# SparkFun_tDof-TMF8820_Mini.net
KiCad netlist of a schematic drawn in EAGLE
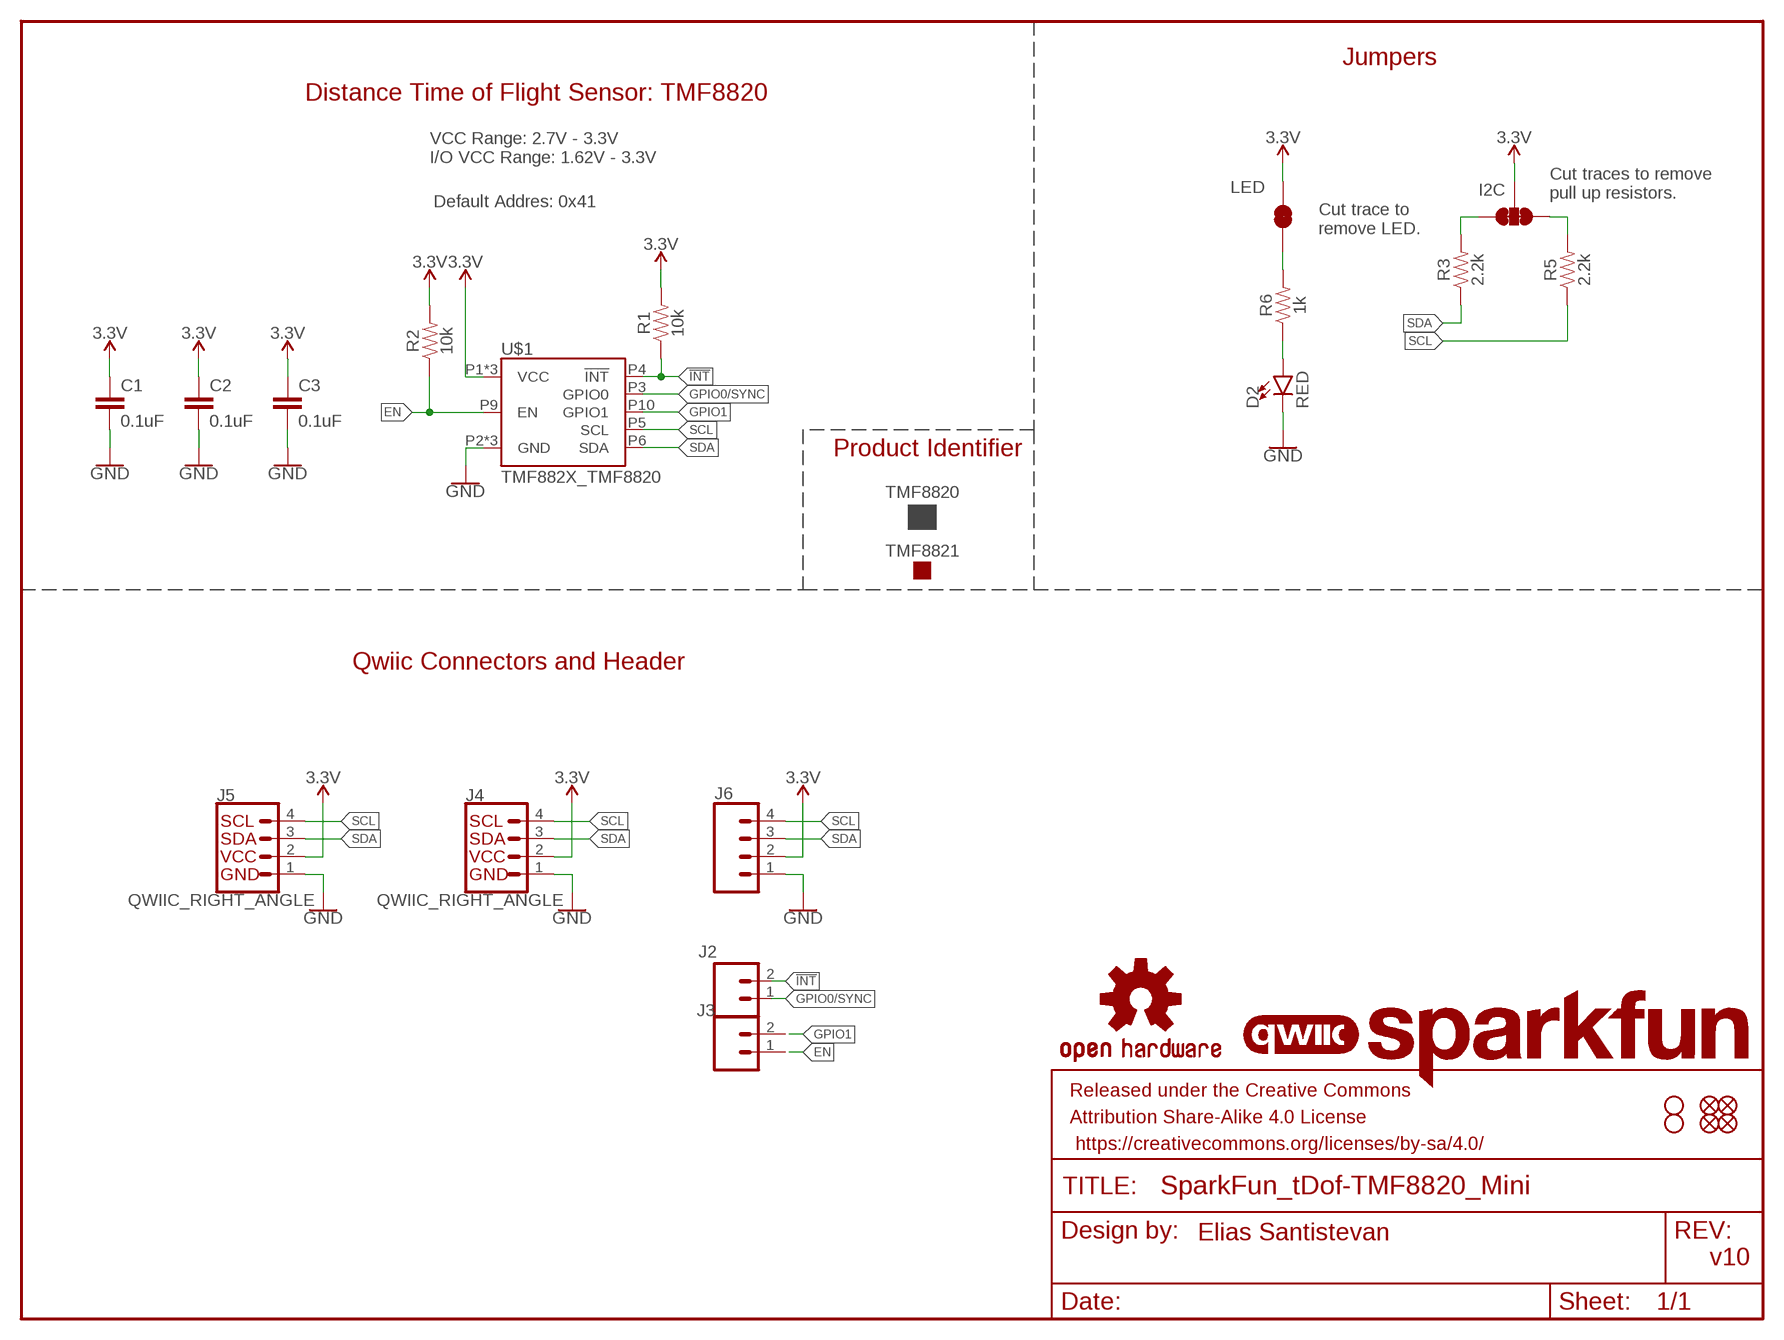
[diagram p0: schematic, sheet 1]

(export (version "E")
  (design (tool "Eeschema 10.0.6"))
  (components
    (comp (ref "C1")
      (value "0.1uF")
      (footprint "eagle-import:0402-TIGHT")
      (libsource (lib "eagle-import") (part "0.1UF-0402T-6.3V-10%-X7R"))
    )
    (comp (ref "C2")
      (value "0.1uF")
      (footprint "eagle-import:0402-TIGHT")
      (libsource (lib "eagle-import") (part "0.1UF-0402T-6.3V-10%-X7R"))
    )
    (comp (ref "C3")
      (value "0.1uF")
      (footprint "eagle-import:0402-TIGHT")
      (libsource (lib "eagle-import") (part "0.1UF-0402T-6.3V-10%-X7R"))
    )
    (comp (ref "D2")
      (value "RED")
      (footprint "eagle-import:LED-0603")
      (libsource (lib "eagle-import") (part "LED-RED0603"))
    )
    (comp (ref "FD5")
      (value "FIDUCIALUFIDUCIAL")
      (footprint "eagle-import:FIDUCIAL-MICRO")
      (libsource (lib "eagle-import") (part "FIDUCIALUFIDUCIAL"))
    )
    (comp (ref "FD6")
      (value "FIDUCIALUFIDUCIAL")
      (footprint "eagle-import:FIDUCIAL-MICRO")
      (libsource (lib "eagle-import") (part "FIDUCIALUFIDUCIAL"))
    )
    (comp (ref "FD7")
      (value "FIDUCIALUFIDUCIAL")
      (footprint "eagle-import:FIDUCIAL-MICRO")
      (libsource (lib "eagle-import") (part "FIDUCIALUFIDUCIAL"))
    )
    (comp (ref "FD8")
      (value "FIDUCIALUFIDUCIAL")
      (footprint "eagle-import:FIDUCIAL-MICRO")
      (libsource (lib "eagle-import") (part "FIDUCIALUFIDUCIAL"))
    )
    (comp (ref "FRAME2")
      (value "FRAME-LETTER")
      (footprint "eagle-import:CREATIVE_COMMONS")
      (libsource (lib "eagle-import") (part "FRAME-LETTER"))
    )
    (comp (ref "H7")
      (value "STAND-OFFTIGHT")
      (footprint "eagle-import:STAND-OFF-TIGHT")
      (libsource (lib "eagle-import") (part "STAND-OFFTIGHT"))
    )
    (comp (ref "H8")
      (value "STAND-OFFTIGHT")
      (footprint "eagle-import:STAND-OFF-TIGHT")
      (libsource (lib "eagle-import") (part "STAND-OFFTIGHT"))
    )
    (comp (ref "I2C")
      (value "I2C_PU")
      (footprint "eagle-import:SMT-JUMPER_3_2-NC_TRACE_SILK")
      (libsource (lib "eagle-import") (part "JUMPER-SMT_3_2-NC_TRACE_SILK"))
    )
    (comp (ref "J2")
      (value "CONN_021X02_NO_SILK")
      (footprint "eagle-import:1X02_NO_SILK")
      (libsource (lib "eagle-import") (part "CONN_021X02_NO_SILK"))
    )
    (comp (ref "J3")
      (value "CONN_021X02_NO_SILK")
      (footprint "eagle-import:1X02_NO_SILK")
      (libsource (lib "eagle-import") (part "CONN_021X02_NO_SILK"))
    )
    (comp (ref "J4")
      (value "QWIIC_RIGHT_ANGLE")
      (footprint "eagle-import:JST04_1MM_RA")
      (libsource (lib "eagle-import") (part "QWIIC_CONNECTORJS-1MM"))
    )
    (comp (ref "J5")
      (value "QWIIC_RIGHT_ANGLE")
      (footprint "eagle-import:JST04_1MM_RA")
      (libsource (lib "eagle-import") (part "QWIIC_CONNECTORJS-1MM"))
    )
    (comp (ref "J6")
      (value "CONN_041X04_NO_SILK")
      (footprint "eagle-import:1X04_NO_SILK")
      (libsource (lib "eagle-import") (part "CONN_041X04_NO_SILK"))
    )
    (comp (ref "LED")
      (value "LED")
      (footprint "eagle-import:SMT-JUMPER_2_NC_TRACE_SILK")
      (libsource (lib "eagle-import") (part "JUMPER-SMT_2_NC_TRACE_SILK"))
    )
    (comp (ref "LOGO1")
      (value "SFE_LOGO_NAMEBLANK")
      (footprint "eagle-import:BLANK")
      (libsource (lib "eagle-import") (part "SFE_LOGO_NAMEBLANK"))
    )
    (comp (ref "LOGO2")
      (value "QWIIC_LOGO_4MM")
      (footprint "eagle-import:QWIIC_4MM")
      (libsource (lib "eagle-import") (part "QWIIC_LOGO_4MM"))
    )
    (comp (ref "LOGO3")
      (value "OSHW-LOGONO_SILK")
      (footprint "eagle-import:DUMMY")
      (libsource (lib "eagle-import") (part "OSHW-LOGONO_SILK"))
    )
    (comp (ref "R1")
      (value "10k")
      (footprint "eagle-import:0402-TIGHT")
      (libsource (lib "eagle-import") (part "10KOHM-0402T-1/16W-1%"))
    )
    (comp (ref "R2")
      (value "10k")
      (footprint "eagle-import:0402-TIGHT")
      (libsource (lib "eagle-import") (part "10KOHM-0402T-1/16W-1%"))
    )
    (comp (ref "R3")
      (value "2.2k")
      (footprint "eagle-import:0402-TIGHT")
      (libsource (lib "eagle-import") (part "2.2KOHM-0402T-1/16W-1%"))
    )
    (comp (ref "R5")
      (value "2.2k")
      (footprint "eagle-import:0402-TIGHT")
      (libsource (lib "eagle-import") (part "2.2KOHM-0402T-1/16W-1%"))
    )
    (comp (ref "R6")
      (value "1k")
      (footprint "eagle-import:0402-TIGHT")
      (libsource (lib "eagle-import") (part "1KOHM-0402T-1/16W-1%"))
    )
    (comp (ref "TMF8820")
      (value "PROD_ID_PASTE_SILK")
      (footprint "eagle-import:PRODUCT_IDENT_PASTE_SILK")
      (libsource (lib "eagle-import") (part "PROD_ID_PASTE_SILK"))
    )
    (comp (ref "TMF8821")
      (value "PROD_ID_NO-PASTE_SILK")
      (footprint "eagle-import:PRODUCT_IDENT_NO_SILK")
      (libsource (lib "eagle-import") (part "PROD_ID_NO-PASTE_SILK"))
    )
    (comp (ref "U$1")
      (value "TMF882X_TMF8820")
      (footprint "eagle-import:TMF882X")
      (libsource (lib "eagle-import") (part "TMF882X_TMF8820"))
    )
  )
  (nets
    (net (code "1") (name "/~{INT}") (class "Default")
      (node (ref "J2") (pin "2") (pinfunction "2_2") (pintype "passive"))
      (node (ref "R1") (pin "1") (pinfunction "1_1") (pintype "passive"))
      (node (ref "U$1") (pin "P4") (pinfunction "~{INT}_P4") (pintype "bidirectional"))
    )
    (net (code "2") (name "3.3V") (class "Default")
      (node (ref "C1") (pin "1") (pinfunction "1_1") (pintype "passive"))
      (node (ref "C2") (pin "1") (pinfunction "1_1") (pintype "passive"))
      (node (ref "C3") (pin "1") (pinfunction "1_1") (pintype "passive"))
      (node (ref "I2C") (pin "2") (pinfunction "2_2") (pintype "passive"))
      (node (ref "J4") (pin "2") (pinfunction "2_2") (pintype "power_in"))
      (node (ref "J5") (pin "2") (pinfunction "2_2") (pintype "power_in"))
      (node (ref "J6") (pin "2") (pinfunction "2_2") (pintype "passive"))
      (node (ref "LED") (pin "2") (pinfunction "2_2") (pintype "passive"))
      (node (ref "R1") (pin "2") (pinfunction "2_2") (pintype "passive"))
      (node (ref "R2") (pin "2") (pinfunction "2_2") (pintype "passive"))
      (node (ref "U$1") (pin "P1") (pinfunction "VCC_P1") (pintype "power_in"))
      (node (ref "U$1") (pin "P12") (pinfunction "VCC_P12") (pintype "power_in"))
      (node (ref "U$1") (pin "P7") (pinfunction "VCC_P7") (pintype "power_in"))
    )
    (net (code "3") (name "EN") (class "Default")
      (node (ref "J3") (pin "1") (pinfunction "1_1") (pintype "passive"))
      (node (ref "R2") (pin "1") (pinfunction "1_1") (pintype "passive"))
      (node (ref "U$1") (pin "P9") (pinfunction "EN_P9") (pintype "input"))
    )
    (net (code "4") (name "GND") (class "Default")
      (node (ref "C1") (pin "2") (pinfunction "2_2") (pintype "passive"))
      (node (ref "C2") (pin "2") (pinfunction "2_2") (pintype "passive"))
      (node (ref "C3") (pin "2") (pinfunction "2_2") (pintype "passive"))
      (node (ref "D2") (pin "C") (pinfunction "C_C") (pintype "passive"))
      (node (ref "J4") (pin "1") (pinfunction "1_1") (pintype "power_in"))
      (node (ref "J5") (pin "1") (pinfunction "1_1") (pintype "power_in"))
      (node (ref "J6") (pin "1") (pinfunction "1_1") (pintype "passive"))
      (node (ref "U$1") (pin "P11") (pinfunction "GND_P11") (pintype "power_in"))
      (node (ref "U$1") (pin "P2") (pinfunction "GND_P2") (pintype "power_in"))
      (node (ref "U$1") (pin "P8") (pinfunction "GND_P8") (pintype "power_in"))
    )
    (net (code "5") (name "GPIO0{slash}SYNC") (class "Default")
      (node (ref "J2") (pin "1") (pinfunction "1_1") (pintype "passive"))
      (node (ref "U$1") (pin "P3") (pinfunction "GPIO0_P3") (pintype "bidirectional"))
    )
    (net (code "6") (name "GPIO1") (class "Default")
      (node (ref "J3") (pin "2") (pinfunction "2_2") (pintype "passive"))
      (node (ref "U$1") (pin "P10") (pinfunction "GPIO1_P10") (pintype "bidirectional"))
    )
    (net (code "7") (name "Net-(D2-PadA)") (class "Default")
      (node (ref "D2") (pin "A") (pinfunction "A_A") (pintype "passive"))
      (node (ref "R6") (pin "1") (pinfunction "1_1") (pintype "passive"))
    )
    (net (code "8") (name "Net-(I2C-Pad1)") (class "Default")
      (node (ref "I2C") (pin "1") (pinfunction "1_1") (pintype "passive"))
      (node (ref "R5") (pin "2") (pinfunction "2_2") (pintype "passive"))
    )
    (net (code "9") (name "Net-(I2C-Pad3)") (class "Default")
      (node (ref "I2C") (pin "3") (pinfunction "3_3") (pintype "passive"))
      (node (ref "R3") (pin "2") (pinfunction "2_2") (pintype "passive"))
    )
    (net (code "10") (name "Net-(LED-Pad1)") (class "Default")
      (node (ref "LED") (pin "1") (pinfunction "1_1") (pintype "passive"))
      (node (ref "R6") (pin "2") (pinfunction "2_2") (pintype "passive"))
    )
    (net (code "11") (name "SCL") (class "Default")
      (node (ref "J4") (pin "4") (pinfunction "4_4") (pintype "passive"))
      (node (ref "J5") (pin "4") (pinfunction "4_4") (pintype "passive"))
      (node (ref "J6") (pin "4") (pinfunction "4_4") (pintype "passive"))
      (node (ref "R5") (pin "1") (pinfunction "1_1") (pintype "passive"))
      (node (ref "U$1") (pin "P5") (pinfunction "SCL_P5") (pintype "bidirectional"))
    )
    (net (code "12") (name "SDA") (class "Default")
      (node (ref "J4") (pin "3") (pinfunction "3_3") (pintype "passive"))
      (node (ref "J5") (pin "3") (pinfunction "3_3") (pintype "passive"))
      (node (ref "J6") (pin "3") (pinfunction "3_3") (pintype "passive"))
      (node (ref "R3") (pin "1") (pinfunction "1_1") (pintype "passive"))
      (node (ref "U$1") (pin "P6") (pinfunction "SDA_P6") (pintype "bidirectional"))
    )
  )
)
